# notes2d2.net
KiCad netlist of a schematic drawn in EAGLE
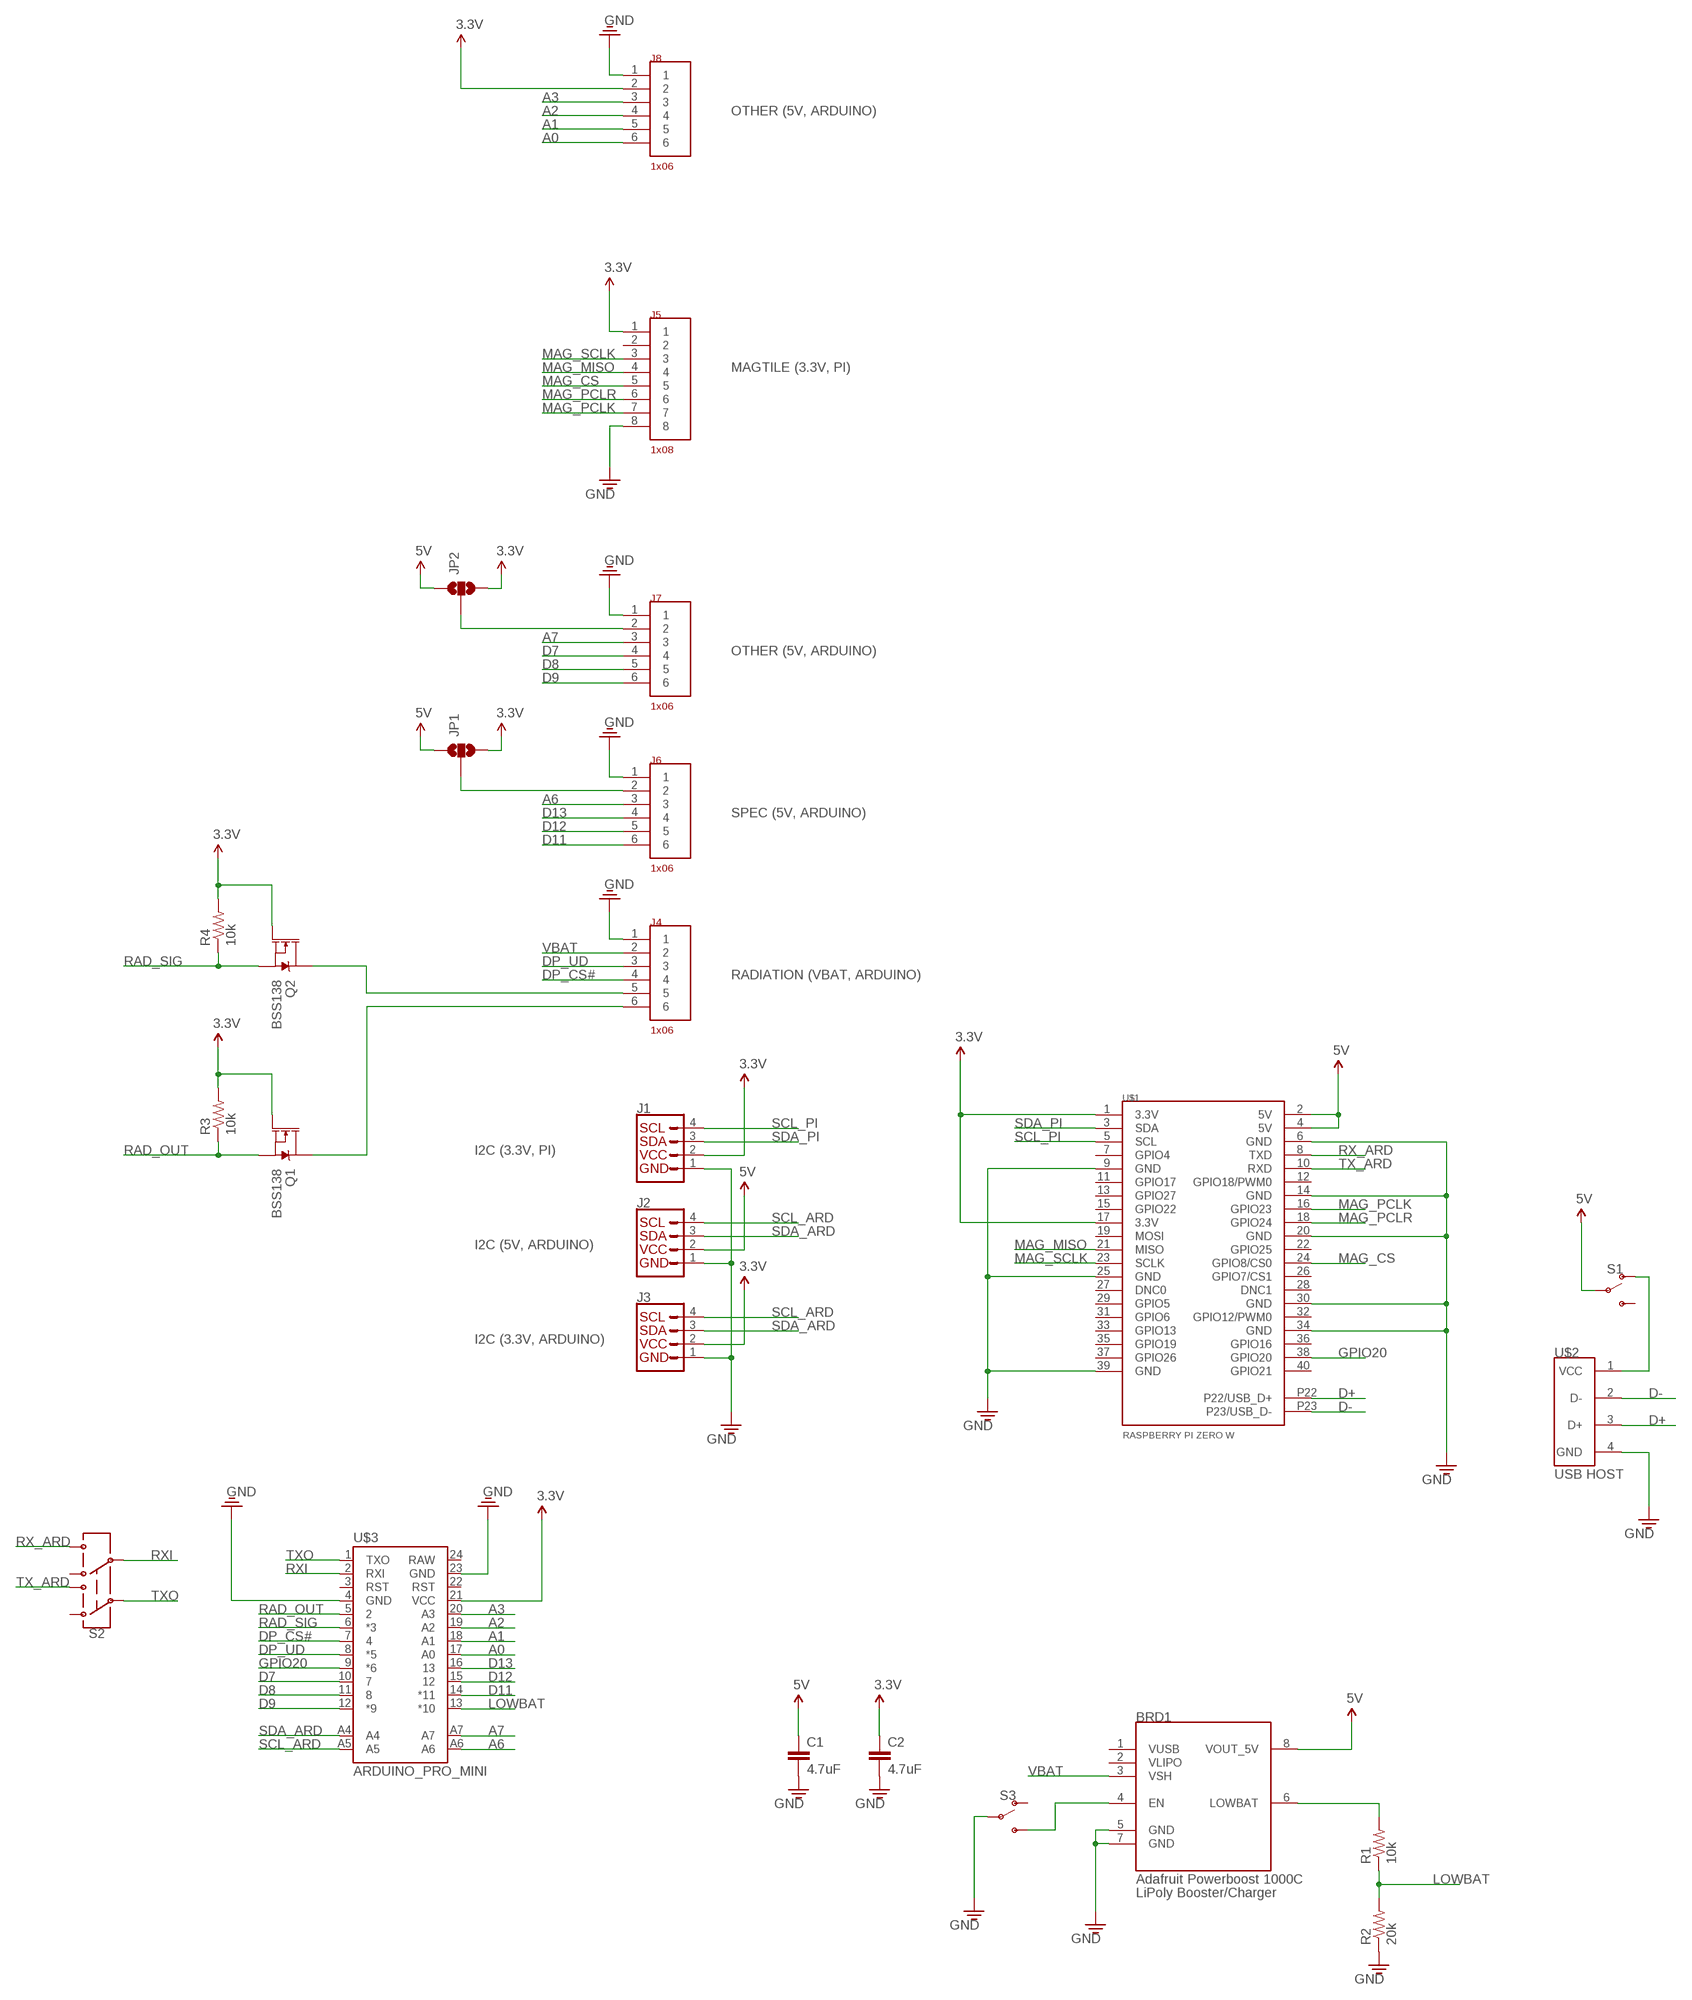
[diagram p0: schematic, sheet 1]

(export (version "E")
  (design (tool "Eeschema 10.0.6"))
  (components
    (comp (ref "BRD1")
      (value "ADAFRUIT_POWERBOOST_1000C")
      (footprint "eagle-import:ADAFRUIT_POWERBOOST_1000C")
      (libsource (lib "eagle-import") (part "ADAFRUIT_POWERBOOST_1000C"))
    )
    (comp (ref "C1")
      (value "4.7uF")
      (footprint "eagle-import:0603")
      (libsource (lib "eagle-import") (part "CAP0603"))
    )
    (comp (ref "C2")
      (value "4.7uF")
      (footprint "eagle-import:0603")
      (libsource (lib "eagle-import") (part "CAP0603"))
    )
    (comp (ref "J1")
      (value "QWIIC_CONNECTORJS-1MM")
      (footprint "eagle-import:1X04_1MM_RA")
      (libsource (lib "eagle-import") (part "QWIIC_CONNECTORJS-1MM"))
    )
    (comp (ref "J2")
      (value "QWIIC_CONNECTORJS-1MM")
      (footprint "eagle-import:1X04_1MM_RA")
      (libsource (lib "eagle-import") (part "QWIIC_CONNECTORJS-1MM"))
    )
    (comp (ref "J3")
      (value "QWIIC_CONNECTORJS-1MM")
      (footprint "eagle-import:1X04_1MM_RA")
      (libsource (lib "eagle-import") (part "QWIIC_CONNECTORJS-1MM"))
    )
    (comp (ref "J4")
      (value "1X06")
      (footprint "eagle-import:JST-SM06B-1MM")
      (libsource (lib "eagle-import") (part "1X06"))
    )
    (comp (ref "J5")
      (value "1X08")
      (footprint "eagle-import:JST-SM08B-1MM")
      (libsource (lib "eagle-import") (part "1X08"))
    )
    (comp (ref "J6")
      (value "1X06")
      (footprint "eagle-import:JST-SM06B-1MM")
      (libsource (lib "eagle-import") (part "1X06"))
    )
    (comp (ref "J7")
      (value "1X06")
      (footprint "eagle-import:JST-SM06B-1MM")
      (libsource (lib "eagle-import") (part "1X06"))
    )
    (comp (ref "J8")
      (value "1X06")
      (footprint "eagle-import:JST-SM06B-1MM")
      (libsource (lib "eagle-import") (part "1X06"))
    )
    (comp (ref "JP1")
      (value "JUMPER-SMT_3_NO_SILK")
      (footprint "eagle-import:SMT-JUMPER_3_NO_SILK")
      (libsource (lib "eagle-import") (part "JUMPER-SMT_3_NO_SILK"))
    )
    (comp (ref "JP2")
      (value "JUMPER-SMT_3_NO_SILK")
      (footprint "eagle-import:SMT-JUMPER_3_NO_SILK")
      (libsource (lib "eagle-import") (part "JUMPER-SMT_3_NO_SILK"))
    )
    (comp (ref "Q1")
      (value "BSS138")
      (footprint "eagle-import:SOT23-3")
      (libsource (lib "eagle-import") (part "MOSFET-NCH-BSS138"))
    )
    (comp (ref "Q2")
      (value "BSS138")
      (footprint "eagle-import:SOT23-3")
      (libsource (lib "eagle-import") (part "MOSFET-NCH-BSS138"))
    )
    (comp (ref "R1")
      (value "10k")
      (footprint "eagle-import:0603")
      (libsource (lib "eagle-import") (part "RESISTOR0603"))
    )
    (comp (ref "R2")
      (value "20k")
      (footprint "eagle-import:0603")
      (libsource (lib "eagle-import") (part "RESISTOR0603"))
    )
    (comp (ref "R3")
      (value "10k")
      (footprint "eagle-import:0603")
      (libsource (lib "eagle-import") (part "RESISTOR0603"))
    )
    (comp (ref "R4")
      (value "10k")
      (footprint "eagle-import:0603")
      (libsource (lib "eagle-import") (part "RESISTOR0603"))
    )
    (comp (ref "S1")
      (value "SWITCH-SPDT-SMD-RIGHT-ANGLE")
      (footprint "eagle-import:SWITCH_SPST_SMD_A")
      (libsource (lib "eagle-import") (part "SWITCH-SPDT-SMD-RIGHT-ANGLE"))
    )
    (comp (ref "S2")
      (value "SWITCH-DPDT-SMD-AYZ0202")
      (footprint "eagle-import:SWITCH_DPDT_SMD_AYZ0202")
      (libsource (lib "eagle-import") (part "SWITCH-DPDT-SMD-AYZ0202"))
    )
    (comp (ref "S3")
      (value "SWITCH-SPDT-SMD-RIGHT-ANGLE")
      (footprint "eagle-import:SWITCH_SPST_SMD_A")
      (libsource (lib "eagle-import") (part "SWITCH-SPDT-SMD-RIGHT-ANGLE"))
    )
    (comp (ref "U$1")
      (value "RASPBERRY-PI-ZEROW-USB")
      (footprint "eagle-import:RASPBERRY-PI-ZEROW-USB")
      (libsource (lib "eagle-import") (part "RASPBERRY-PI-ZEROW-USB"))
    )
    (comp (ref "U$2")
      (value "USB-HOST")
      (footprint "eagle-import:1-292303-6")
      (libsource (lib "eagle-import") (part "USB-HOST"))
    )
    (comp (ref "U$3")
      (value "ARDUINO_PRO_MINI")
      (footprint "eagle-import:ARDUINO_PRO_MINI")
      (libsource (lib "eagle-import") (part "ARDUINO_PRO_MINI"))
    )
  )
  (nets
    (net (code "1") (name "/A0") (class "Default")
      (node (ref "J8") (pin "6") (pinfunction "6_6") (pintype "bidirectional"))
      (node (ref "U$3") (pin "17") (pinfunction "A0_17") (pintype "bidirectional"))
    )
    (net (code "2") (name "/A1") (class "Default")
      (node (ref "J8") (pin "5") (pinfunction "5_5") (pintype "bidirectional"))
      (node (ref "U$3") (pin "18") (pinfunction "A1_18") (pintype "bidirectional"))
    )
    (net (code "3") (name "/A2") (class "Default")
      (node (ref "J8") (pin "4") (pinfunction "4_4") (pintype "bidirectional"))
      (node (ref "U$3") (pin "19") (pinfunction "A2_19") (pintype "bidirectional"))
    )
    (net (code "4") (name "/A3") (class "Default")
      (node (ref "J8") (pin "3") (pinfunction "3_3") (pintype "bidirectional"))
      (node (ref "U$3") (pin "20") (pinfunction "A3_20") (pintype "bidirectional"))
    )
    (net (code "5") (name "/A6") (class "Default")
      (node (ref "J6") (pin "3") (pinfunction "3_3") (pintype "bidirectional"))
      (node (ref "U$3") (pin "A6") (pinfunction "A6_A6") (pintype "bidirectional"))
    )
    (net (code "6") (name "/A7") (class "Default")
      (node (ref "J7") (pin "3") (pinfunction "3_3") (pintype "bidirectional"))
      (node (ref "U$3") (pin "A7") (pinfunction "A7_A7") (pintype "bidirectional"))
    )
    (net (code "7") (name "/D+") (class "Default")
      (node (ref "U$1") (pin "P22") (pinfunction "P22/USB_D+_P22") (pintype "bidirectional"))
      (node (ref "U$2") (pin "3") (pinfunction "D+_3") (pintype "bidirectional"))
    )
    (net (code "8") (name "/D-") (class "Default")
      (node (ref "U$1") (pin "P23") (pinfunction "P23/USB_D-_P23") (pintype "bidirectional"))
      (node (ref "U$2") (pin "2") (pinfunction "D-_2") (pintype "bidirectional"))
    )
    (net (code "9") (name "/D7") (class "Default")
      (node (ref "J7") (pin "4") (pinfunction "4_4") (pintype "bidirectional"))
      (node (ref "U$3") (pin "10") (pinfunction "7_10") (pintype "bidirectional"))
    )
    (net (code "10") (name "/D8") (class "Default")
      (node (ref "J7") (pin "5") (pinfunction "5_5") (pintype "bidirectional"))
      (node (ref "U$3") (pin "11") (pinfunction "8_11") (pintype "bidirectional"))
    )
    (net (code "11") (name "/D9") (class "Default")
      (node (ref "J7") (pin "6") (pinfunction "6_6") (pintype "bidirectional"))
      (node (ref "U$3") (pin "12") (pinfunction "*9_12") (pintype "bidirectional"))
    )
    (net (code "12") (name "/D11") (class "Default")
      (node (ref "J6") (pin "6") (pinfunction "6_6") (pintype "bidirectional"))
      (node (ref "U$3") (pin "14") (pinfunction "*11_14") (pintype "bidirectional"))
    )
    (net (code "13") (name "/D12") (class "Default")
      (node (ref "J6") (pin "5") (pinfunction "5_5") (pintype "bidirectional"))
      (node (ref "U$3") (pin "15") (pinfunction "12_15") (pintype "bidirectional"))
    )
    (net (code "14") (name "/D13") (class "Default")
      (node (ref "J6") (pin "4") (pinfunction "4_4") (pintype "bidirectional"))
      (node (ref "U$3") (pin "16") (pinfunction "13_16") (pintype "bidirectional"))
    )
    (net (code "15") (name "/DP_CS#") (class "Default")
      (node (ref "J4") (pin "4") (pinfunction "4_4") (pintype "bidirectional"))
      (node (ref "U$3") (pin "7") (pinfunction "4_7") (pintype "bidirectional"))
    )
    (net (code "16") (name "/DP_UD") (class "Default")
      (node (ref "J4") (pin "3") (pinfunction "3_3") (pintype "bidirectional"))
      (node (ref "U$3") (pin "8") (pinfunction "*5_8") (pintype "bidirectional"))
    )
    (net (code "17") (name "/GPIO20") (class "Default")
      (node (ref "U$1") (pin "38") (pinfunction "GPIO20_38") (pintype "bidirectional"))
      (node (ref "U$3") (pin "9") (pinfunction "*6_9") (pintype "bidirectional"))
    )
    (net (code "18") (name "/LOWBAT") (class "Default")
      (node (ref "R1") (pin "1") (pinfunction "1_1") (pintype "passive"))
      (node (ref "R2") (pin "2") (pinfunction "2_2") (pintype "passive"))
      (node (ref "U$3") (pin "13") (pinfunction "*10_13") (pintype "bidirectional"))
    )
    (net (code "19") (name "/MAG_CS") (class "Default")
      (node (ref "J5") (pin "5") (pinfunction "5_5") (pintype "bidirectional"))
      (node (ref "U$1") (pin "24") (pinfunction "GPIO8/CS0_24") (pintype "bidirectional"))
    )
    (net (code "20") (name "/MAG_MISO") (class "Default")
      (node (ref "J5") (pin "4") (pinfunction "4_4") (pintype "bidirectional"))
      (node (ref "U$1") (pin "21") (pinfunction "MISO_21") (pintype "bidirectional"))
    )
    (net (code "21") (name "/MAG_PCLK") (class "Default")
      (node (ref "J5") (pin "7") (pinfunction "7_7") (pintype "bidirectional"))
      (node (ref "U$1") (pin "16") (pinfunction "GPIO23_16") (pintype "bidirectional"))
    )
    (net (code "22") (name "/MAG_PCLR") (class "Default")
      (node (ref "J5") (pin "6") (pinfunction "6_6") (pintype "bidirectional"))
      (node (ref "U$1") (pin "18") (pinfunction "GPIO24_18") (pintype "bidirectional"))
    )
    (net (code "23") (name "/MAG_SCLK") (class "Default")
      (node (ref "J5") (pin "3") (pinfunction "3_3") (pintype "bidirectional"))
      (node (ref "U$1") (pin "23") (pinfunction "SCLK_23") (pintype "bidirectional"))
    )
    (net (code "24") (name "/RAD_OUT") (class "Default")
      (node (ref "Q1") (pin "2") (pinfunction "S_2") (pintype "bidirectional"))
      (node (ref "R3") (pin "1") (pinfunction "1_1") (pintype "passive"))
      (node (ref "U$3") (pin "5") (pinfunction "2_5") (pintype "bidirectional"))
    )
    (net (code "25") (name "/RAD_SIG") (class "Default")
      (node (ref "Q2") (pin "2") (pinfunction "S_2") (pintype "bidirectional"))
      (node (ref "R4") (pin "1") (pinfunction "1_1") (pintype "passive"))
      (node (ref "U$3") (pin "6") (pinfunction "*3_6") (pintype "bidirectional"))
    )
    (net (code "26") (name "/RXI") (class "Default")
      (node (ref "S2") (pin "5") (pinfunction "5_5") (pintype "bidirectional"))
      (node (ref "U$3") (pin "2") (pinfunction "RXI_2") (pintype "bidirectional"))
    )
    (net (code "27") (name "/RX_ARD") (class "Default")
      (node (ref "S2") (pin "6") (pinfunction "6_6") (pintype "bidirectional"))
      (node (ref "U$1") (pin "8") (pinfunction "TXD_8") (pintype "bidirectional"))
    )
    (net (code "28") (name "/SCL_ARD") (class "Default")
      (node (ref "J2") (pin "4") (pinfunction "SCL_4") (pintype "passive"))
      (node (ref "J3") (pin "4") (pinfunction "SCL_4") (pintype "passive"))
      (node (ref "U$3") (pin "A5") (pinfunction "A5_A5") (pintype "bidirectional"))
    )
    (net (code "29") (name "/SCL_PI") (class "Default")
      (node (ref "J1") (pin "4") (pinfunction "SCL_4") (pintype "passive"))
      (node (ref "U$1") (pin "5") (pinfunction "SCL_5") (pintype "bidirectional"))
    )
    (net (code "30") (name "/SDA_ARD") (class "Default")
      (node (ref "J2") (pin "3") (pinfunction "SDA_3") (pintype "passive"))
      (node (ref "J3") (pin "3") (pinfunction "SDA_3") (pintype "passive"))
      (node (ref "U$3") (pin "A4") (pinfunction "A4_A4") (pintype "bidirectional"))
    )
    (net (code "31") (name "/SDA_PI") (class "Default")
      (node (ref "J1") (pin "3") (pinfunction "SDA_3") (pintype "passive"))
      (node (ref "U$1") (pin "3") (pinfunction "SDA_3") (pintype "bidirectional"))
    )
    (net (code "32") (name "/TXO") (class "Default")
      (node (ref "S2") (pin "2") (pinfunction "2_2") (pintype "bidirectional"))
      (node (ref "U$3") (pin "1") (pinfunction "TXO_1") (pintype "bidirectional"))
    )
    (net (code "33") (name "/TX_ARD") (class "Default")
      (node (ref "S2") (pin "3") (pinfunction "3_3") (pintype "bidirectional"))
      (node (ref "U$1") (pin "10") (pinfunction "RXD_10") (pintype "bidirectional"))
    )
    (net (code "34") (name "/VBAT") (class "Default")
      (node (ref "BRD1") (pin "3") (pinfunction "VSH_3") (pintype "bidirectional"))
      (node (ref "J4") (pin "2") (pinfunction "2_2") (pintype "bidirectional"))
    )
    (net (code "35") (name "3.3V") (class "Default")
      (node (ref "C2") (pin "1") (pinfunction "1_1") (pintype "passive"))
      (node (ref "J1") (pin "2") (pinfunction "VCC_2") (pintype "power_in"))
      (node (ref "J3") (pin "2") (pinfunction "VCC_2") (pintype "power_in"))
      (node (ref "J5") (pin "1") (pinfunction "1_1") (pintype "bidirectional"))
      (node (ref "J8") (pin "2") (pinfunction "2_2") (pintype "bidirectional"))
      (node (ref "JP1") (pin "3") (pinfunction "3_3") (pintype "passive"))
      (node (ref "JP2") (pin "3") (pinfunction "3_3") (pintype "passive"))
      (node (ref "Q1") (pin "1") (pinfunction "G_1") (pintype "bidirectional"))
      (node (ref "Q2") (pin "1") (pinfunction "G_1") (pintype "bidirectional"))
      (node (ref "R3") (pin "2") (pinfunction "2_2") (pintype "passive"))
      (node (ref "R4") (pin "2") (pinfunction "2_2") (pintype "passive"))
      (node (ref "U$1") (pin "1") (pinfunction "3.3V_1") (pintype "bidirectional"))
      (node (ref "U$1") (pin "17") (pinfunction "3.3V_17") (pintype "bidirectional"))
      (node (ref "U$3") (pin "21") (pinfunction "VCC_21") (pintype "bidirectional"))
    )
    (net (code "36") (name "5V") (class "Default")
      (node (ref "BRD1") (pin "8") (pinfunction "VOUT_5V_8") (pintype "bidirectional"))
      (node (ref "C1") (pin "1") (pinfunction "1_1") (pintype "passive"))
      (node (ref "J2") (pin "2") (pinfunction "VCC_2") (pintype "power_in"))
      (node (ref "JP1") (pin "1") (pinfunction "1_1") (pintype "passive"))
      (node (ref "JP2") (pin "1") (pinfunction "1_1") (pintype "passive"))
      (node (ref "S1") (pin "2") (pinfunction "P_2") (pintype "passive"))
      (node (ref "U$1") (pin "2") (pinfunction "5V_2") (pintype "bidirectional"))
      (node (ref "U$1") (pin "4") (pinfunction "5V_4") (pintype "bidirectional"))
    )
    (net (code "37") (name "GND") (class "Default")
      (node (ref "BRD1") (pin "5") (pinfunction "GND_5") (pintype "bidirectional"))
      (node (ref "BRD1") (pin "7") (pinfunction "GND_7") (pintype "bidirectional"))
      (node (ref "C1") (pin "2") (pinfunction "2_2") (pintype "passive"))
      (node (ref "C2") (pin "2") (pinfunction "2_2") (pintype "passive"))
      (node (ref "J1") (pin "1") (pinfunction "GND_1") (pintype "power_in"))
      (node (ref "J2") (pin "1") (pinfunction "GND_1") (pintype "power_in"))
      (node (ref "J3") (pin "1") (pinfunction "GND_1") (pintype "power_in"))
      (node (ref "J4") (pin "1") (pinfunction "1_1") (pintype "bidirectional"))
      (node (ref "J5") (pin "8") (pinfunction "8_8") (pintype "bidirectional"))
      (node (ref "J6") (pin "1") (pinfunction "1_1") (pintype "bidirectional"))
      (node (ref "J7") (pin "1") (pinfunction "1_1") (pintype "bidirectional"))
      (node (ref "J8") (pin "1") (pinfunction "1_1") (pintype "bidirectional"))
      (node (ref "R2") (pin "1") (pinfunction "1_1") (pintype "passive"))
      (node (ref "S3") (pin "2") (pinfunction "P_2") (pintype "passive"))
      (node (ref "U$1") (pin "14") (pinfunction "GND_14") (pintype "bidirectional"))
      (node (ref "U$1") (pin "20") (pinfunction "GND_20") (pintype "bidirectional"))
      (node (ref "U$1") (pin "25") (pinfunction "GND_25") (pintype "bidirectional"))
      (node (ref "U$1") (pin "30") (pinfunction "GND_30") (pintype "bidirectional"))
      (node (ref "U$1") (pin "34") (pinfunction "GND_34") (pintype "bidirectional"))
      (node (ref "U$1") (pin "39") (pinfunction "GND_39") (pintype "bidirectional"))
      (node (ref "U$1") (pin "6") (pinfunction "GND_6") (pintype "bidirectional"))
      (node (ref "U$1") (pin "9") (pinfunction "GND_9") (pintype "bidirectional"))
      (node (ref "U$2") (pin "4") (pinfunction "GND_4") (pintype "bidirectional"))
      (node (ref "U$3") (pin "23") (pinfunction "GND_23") (pintype "bidirectional"))
      (node (ref "U$3") (pin "4") (pinfunction "GND_4") (pintype "bidirectional"))
    )
    (net (code "38") (name "Net-(BRD1-EN)") (class "Default")
      (node (ref "BRD1") (pin "4") (pinfunction "EN_4") (pintype "bidirectional"))
      (node (ref "S3") (pin "3") (pinfunction "S_3") (pintype "passive"))
    )
    (net (code "39") (name "Net-(BRD1-LOWBAT)") (class "Default")
      (node (ref "BRD1") (pin "6") (pinfunction "LOWBAT_6") (pintype "bidirectional"))
      (node (ref "R1") (pin "2") (pinfunction "2_2") (pintype "passive"))
    )
    (net (code "40") (name "Net-(J6-Pad2)") (class "Default")
      (node (ref "J6") (pin "2") (pinfunction "2_2") (pintype "bidirectional"))
      (node (ref "JP1") (pin "2") (pinfunction "2_2") (pintype "passive"))
    )
    (net (code "41") (name "Net-(J7-Pad2)") (class "Default")
      (node (ref "J7") (pin "2") (pinfunction "2_2") (pintype "bidirectional"))
      (node (ref "JP2") (pin "2") (pinfunction "2_2") (pintype "passive"))
    )
    (net (code "42") (name "Net-(Q1-D)") (class "Default")
      (node (ref "J4") (pin "6") (pinfunction "6_6") (pintype "bidirectional"))
      (node (ref "Q1") (pin "3") (pinfunction "D_3") (pintype "bidirectional"))
    )
    (net (code "43") (name "Net-(Q2-D)") (class "Default")
      (node (ref "J4") (pin "5") (pinfunction "5_5") (pintype "bidirectional"))
      (node (ref "Q2") (pin "3") (pinfunction "D_3") (pintype "bidirectional"))
    )
    (net (code "44") (name "Net-(S1-O)") (class "Default")
      (node (ref "S1") (pin "1") (pinfunction "O_1") (pintype "passive"))
      (node (ref "U$2") (pin "1") (pinfunction "VCC_1") (pintype "bidirectional"))
    )
    (net (code "45") (name "unconnected-(BRD1-VLIPO-Pad2)") (class "Default")
      (node (ref "BRD1") (pin "2") (pinfunction "VLIPO_2") (pintype "bidirectional"))
    )
    (net (code "46") (name "unconnected-(BRD1-VUSB-Pad1)") (class "Default")
      (node (ref "BRD1") (pin "1") (pinfunction "VUSB_1") (pintype "bidirectional"))
    )
    (net (code "47") (name "unconnected-(J5-Pad2)") (class "Default")
      (node (ref "J5") (pin "2") (pinfunction "2_2") (pintype "bidirectional"))
    )
    (net (code "48") (name "unconnected-(S1-S-Pad3)") (class "Default")
      (node (ref "S1") (pin "3") (pinfunction "S_3") (pintype "passive"))
    )
    (net (code "49") (name "unconnected-(S2-Pad1)") (class "Default")
      (node (ref "S2") (pin "1") (pinfunction "1_1") (pintype "bidirectional"))
    )
    (net (code "50") (name "unconnected-(S2-Pad4)") (class "Default")
      (node (ref "S2") (pin "4") (pinfunction "4_4") (pintype "bidirectional"))
    )
    (net (code "51") (name "unconnected-(S3-O-Pad1)") (class "Default")
      (node (ref "S3") (pin "1") (pinfunction "O_1") (pintype "passive"))
    )
    (net (code "52") (name "unconnected-(U$1-DNC0-Pad27)") (class "Default")
      (node (ref "U$1") (pin "27") (pinfunction "DNC0_27") (pintype "bidirectional"))
    )
    (net (code "53") (name "unconnected-(U$1-DNC1-Pad28)") (class "Default")
      (node (ref "U$1") (pin "28") (pinfunction "DNC1_28") (pintype "bidirectional"))
    )
    (net (code "54") (name "unconnected-(U$1-GPIO4-Pad7)") (class "Default")
      (node (ref "U$1") (pin "7") (pinfunction "GPIO4_7") (pintype "bidirectional"))
    )
    (net (code "55") (name "unconnected-(U$1-GPIO5-Pad29)") (class "Default")
      (node (ref "U$1") (pin "29") (pinfunction "GPIO5_29") (pintype "bidirectional"))
    )
    (net (code "56") (name "unconnected-(U$1-GPIO6-Pad31)") (class "Default")
      (node (ref "U$1") (pin "31") (pinfunction "GPIO6_31") (pintype "bidirectional"))
    )
    (net (code "57") (name "unconnected-(U$1-GPIO7{slash}CS1-Pad26)") (class "Default")
      (node (ref "U$1") (pin "26") (pinfunction "GPIO7/CS1_26") (pintype "bidirectional"))
    )
    (net (code "58") (name "unconnected-(U$1-GPIO12{slash}PWM0-Pad32)") (class "Default")
      (node (ref "U$1") (pin "32") (pinfunction "GPIO12/PWM0_32") (pintype "bidirectional"))
    )
    (net (code "59") (name "unconnected-(U$1-GPIO13-Pad33)") (class "Default")
      (node (ref "U$1") (pin "33") (pinfunction "GPIO13_33") (pintype "bidirectional"))
    )
    (net (code "60") (name "unconnected-(U$1-GPIO16-Pad36)") (class "Default")
      (node (ref "U$1") (pin "36") (pinfunction "GPIO16_36") (pintype "bidirectional"))
    )
    (net (code "61") (name "unconnected-(U$1-GPIO17-Pad11)") (class "Default")
      (node (ref "U$1") (pin "11") (pinfunction "GPIO17_11") (pintype "bidirectional"))
    )
    (net (code "62") (name "unconnected-(U$1-GPIO18{slash}PWM0-Pad12)") (class "Default")
      (node (ref "U$1") (pin "12") (pinfunction "GPIO18/PWM0_12") (pintype "bidirectional"))
    )
    (net (code "63") (name "unconnected-(U$1-GPIO19-Pad35)") (class "Default")
      (node (ref "U$1") (pin "35") (pinfunction "GPIO19_35") (pintype "bidirectional"))
    )
    (net (code "64") (name "unconnected-(U$1-GPIO21-Pad40)") (class "Default")
      (node (ref "U$1") (pin "40") (pinfunction "GPIO21_40") (pintype "bidirectional"))
    )
    (net (code "65") (name "unconnected-(U$1-GPIO22-Pad15)") (class "Default")
      (node (ref "U$1") (pin "15") (pinfunction "GPIO22_15") (pintype "bidirectional"))
    )
    (net (code "66") (name "unconnected-(U$1-GPIO25-Pad22)") (class "Default")
      (node (ref "U$1") (pin "22") (pinfunction "GPIO25_22") (pintype "bidirectional"))
    )
    (net (code "67") (name "unconnected-(U$1-GPIO26-Pad37)") (class "Default")
      (node (ref "U$1") (pin "37") (pinfunction "GPIO26_37") (pintype "bidirectional"))
    )
    (net (code "68") (name "unconnected-(U$1-GPIO27-Pad13)") (class "Default")
      (node (ref "U$1") (pin "13") (pinfunction "GPIO27_13") (pintype "bidirectional"))
    )
    (net (code "69") (name "unconnected-(U$1-MOSI-Pad19)") (class "Default")
      (node (ref "U$1") (pin "19") (pinfunction "MOSI_19") (pintype "bidirectional"))
    )
    (net (code "70") (name "unconnected-(U$3-RAW-Pad24)") (class "Default")
      (node (ref "U$3") (pin "24") (pinfunction "RAW_24") (pintype "bidirectional"))
    )
    (net (code "71") (name "unconnected-(U$3-RST-Pad3)") (class "Default")
      (node (ref "U$3") (pin "3") (pinfunction "RST_3") (pintype "bidirectional"))
    )
    (net (code "72") (name "unconnected-(U$3-RST-Pad22)") (class "Default")
      (node (ref "U$3") (pin "22") (pinfunction "RST_22") (pintype "bidirectional"))
    )
  )
)
